# capslocker.net
KiCad netlist of a schematic drawn in EAGLE
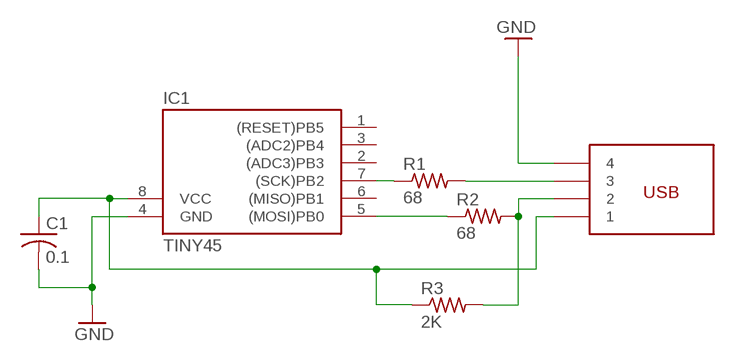
[diagram p0: schematic, sheet 1]

(export (version "E")
  (design (tool "Eeschema 10.0.6"))
  (components
    (comp (ref "C1")
      (value "0.1")
      (footprint "eagle-import:C0805")
      (libsource (lib "eagle-import") (part "C-USC0805"))
    )
    (comp (ref "IC1")
      (value "TINY45")
      (footprint "eagle-import:SOIC8")
      (libsource (lib "eagle-import") (part "TINY45"))
    )
    (comp (ref "R1")
      (value "68")
      (footprint "eagle-import:R0603")
      (libsource (lib "eagle-import") (part "R-US_R0603"))
    )
    (comp (ref "R2")
      (value "68")
      (footprint "eagle-import:R0603")
      (libsource (lib "eagle-import") (part "R-US_R0603"))
    )
    (comp (ref "R3")
      (value "2K")
      (footprint "eagle-import:R0603")
      (libsource (lib "eagle-import") (part "R-US_R0603"))
    )
    (comp (ref "U$1")
      (value "USB_A_EDGE")
      (footprint "eagle-import:USB_A_EDGE")
      (libsource (lib "eagle-import") (part "USB_A_EDGE"))
    )
  )
  (nets
    (net (code "1") (name "GND") (class "Default")
      (node (ref "C1") (pin "2") (pinfunction "2_2") (pintype "passive"))
      (node (ref "IC1") (pin "4") (pinfunction "GND_4") (pintype "power_in"))
      (node (ref "U$1") (pin "P$3") (pinfunction "4_P$3") (pintype "bidirectional"))
    )
    (net (code "2") (name "Net-(IC1-(MOSI)PB0)") (class "Default")
      (node (ref "IC1") (pin "5") (pinfunction "(MOSI)PB0_5") (pintype "bidirectional"))
      (node (ref "R2") (pin "1") (pinfunction "1_1") (pintype "passive"))
    )
    (net (code "3") (name "Net-(IC1-(SCK)PB2)") (class "Default")
      (node (ref "IC1") (pin "7") (pinfunction "(SCK)PB2_7") (pintype "bidirectional"))
      (node (ref "R1") (pin "1") (pinfunction "1_1") (pintype "passive"))
    )
    (net (code "4") (name "Net-(IC1-VCC)") (class "Default")
      (node (ref "C1") (pin "1") (pinfunction "1_1") (pintype "passive"))
      (node (ref "IC1") (pin "8") (pinfunction "VCC_8") (pintype "power_in"))
      (node (ref "R3") (pin "1") (pinfunction "1_1") (pintype "passive"))
      (node (ref "U$1") (pin "P$4") (pinfunction "1_P$4") (pintype "bidirectional"))
    )
    (net (code "5") (name "Net-(U$1-2)") (class "Default")
      (node (ref "R2") (pin "2") (pinfunction "2_2") (pintype "passive"))
      (node (ref "R3") (pin "2") (pinfunction "2_2") (pintype "passive"))
      (node (ref "U$1") (pin "P$2") (pinfunction "2_P$2") (pintype "bidirectional"))
    )
    (net (code "6") (name "Net-(U$1-3)") (class "Default")
      (node (ref "R1") (pin "2") (pinfunction "2_2") (pintype "passive"))
      (node (ref "U$1") (pin "P$1") (pinfunction "3_P$1") (pintype "bidirectional"))
    )
    (net (code "7") (name "unconnected-(IC1-(ADC2)PB4-Pad3)") (class "Default")
      (node (ref "IC1") (pin "3") (pinfunction "(ADC2)PB4_3") (pintype "bidirectional"))
    )
    (net (code "8") (name "unconnected-(IC1-(ADC3)PB3-Pad2)") (class "Default")
      (node (ref "IC1") (pin "2") (pinfunction "(ADC3)PB3_2") (pintype "bidirectional"))
    )
    (net (code "9") (name "unconnected-(IC1-(MISO)PB1-Pad6)") (class "Default")
      (node (ref "IC1") (pin "6") (pinfunction "(MISO)PB1_6") (pintype "bidirectional"))
    )
    (net (code "10") (name "unconnected-(IC1-(RESET)PB5-Pad1)") (class "Default")
      (node (ref "IC1") (pin "1") (pinfunction "(RESET)PB5_1") (pintype "bidirectional"))
    )
  )
)
